# Untitled.net
KiCad netlist of a schematic drawn in EAGLE
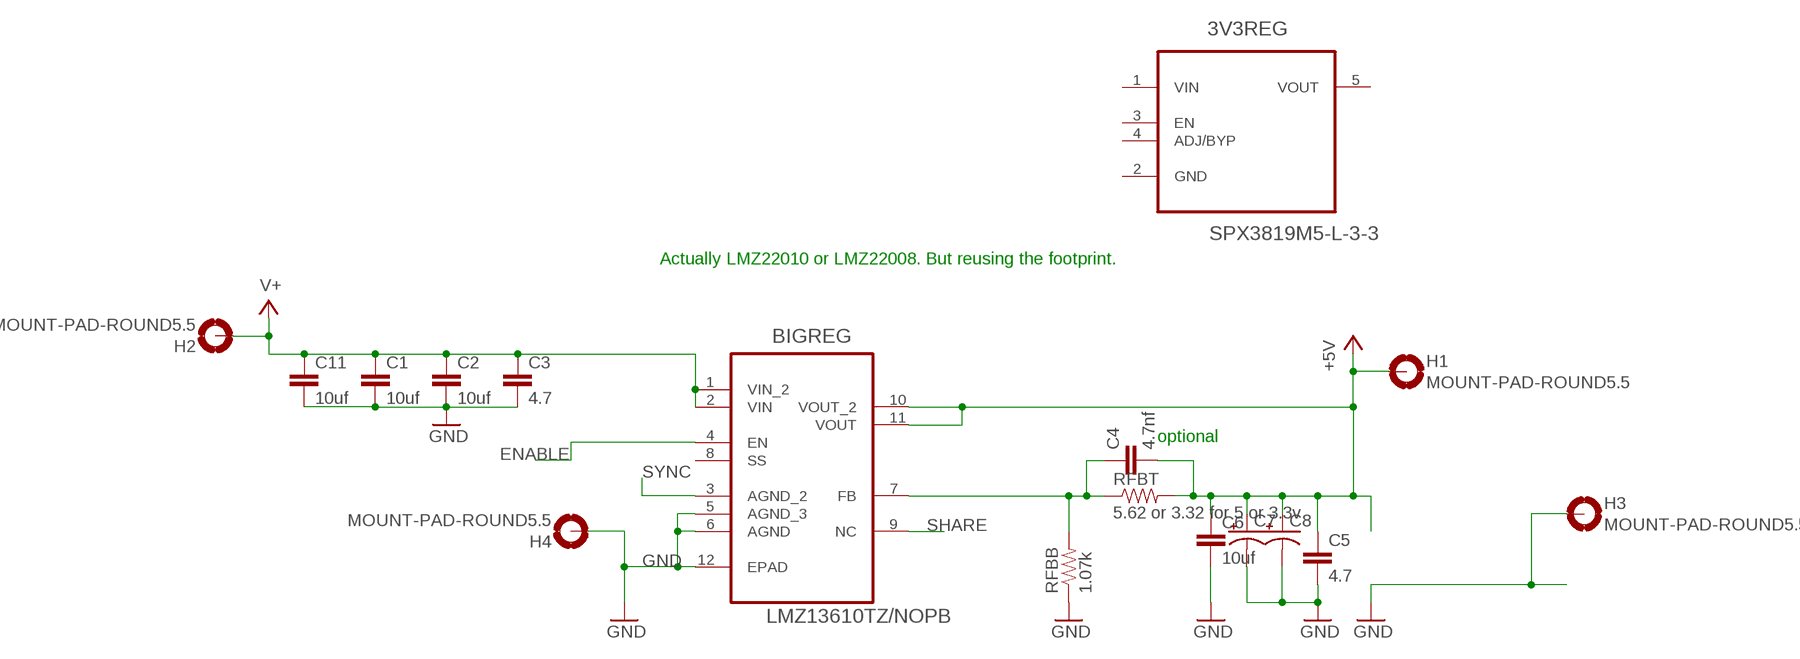
[diagram p0: schematic, sheet 1]

(export (version "E")
  (design (tool "Eeschema 10.0.6"))
  (components
    (comp (ref "3V3REG")
      (value "SPX3819M5-L-3-3")
      (footprint "eagle-import:SOT95P280X145-5N")
      (libsource (lib "eagle-import") (part "SPX3819M5-L-3-3"))
    )
    (comp (ref "BIGREG")
      (value "LMZ13610TZ/NOPB")
      (footprint "eagle-import:TI_TO-PMOD-11")
      (libsource (lib "eagle-import") (part "LMZ13610TZ/NOPB"))
    )
    (comp (ref "C1")
      (value "10uf")
      (footprint "eagle-import:1206")
      (libsource (lib "eagle-import") (part "CAP1206"))
    )
    (comp (ref "C2")
      (value "10uf")
      (footprint "eagle-import:1206")
      (libsource (lib "eagle-import") (part "CAP1206"))
    )
    (comp (ref "C3")
      (value "4.7")
      (footprint "eagle-import:1206")
      (libsource (lib "eagle-import") (part "CAP1206"))
    )
    (comp (ref "C4")
      (value "4.7nf")
      (footprint "eagle-import:0603-CAP")
      (libsource (lib "eagle-import") (part "SparkFun-Passives_CAP0603-CAP"))
    )
    (comp (ref "C5")
      (value "4.7")
      (footprint "eagle-import:1206")
      (libsource (lib "eagle-import") (part "CAP1206"))
    )
    (comp (ref "C6")
      (value "10uf")
      (footprint "eagle-import:1206")
      (libsource (lib "eagle-import") (part "CAP1206"))
    )
    (comp (ref "C7")
      (value "CAP_POLPTH2")
      (footprint "eagle-import:CPOL-RADIAL-10UF-25V")
      (libsource (lib "eagle-import") (part "CAP_POLPTH2"))
    )
    (comp (ref "C8")
      (value "CAP_POLPTH2")
      (footprint "eagle-import:CPOL-RADIAL-10UF-25V")
      (libsource (lib "eagle-import") (part "CAP_POLPTH2"))
    )
    (comp (ref "C11")
      (value "10uf")
      (footprint "eagle-import:1206")
      (libsource (lib "eagle-import") (part "CAP1206"))
    )
    (comp (ref "H1")
      (value "MOUNT-PAD-ROUND5.5")
      (footprint "eagle-import:5,5-PAD")
      (libsource (lib "eagle-import") (part "MOUNT-PAD-ROUND5.5"))
    )
    (comp (ref "H2")
      (value "MOUNT-PAD-ROUND5.5")
      (footprint "eagle-import:5,5-PAD")
      (libsource (lib "eagle-import") (part "MOUNT-PAD-ROUND5.5"))
    )
    (comp (ref "H3")
      (value "MOUNT-PAD-ROUND5.5")
      (footprint "eagle-import:5,5-PAD")
      (libsource (lib "eagle-import") (part "MOUNT-PAD-ROUND5.5"))
    )
    (comp (ref "H4")
      (value "MOUNT-PAD-ROUND5.5")
      (footprint "eagle-import:5,5-PAD")
      (libsource (lib "eagle-import") (part "MOUNT-PAD-ROUND5.5"))
    )
    (comp (ref "RFBB")
      (value "1.07k")
      (footprint "eagle-import:0603-RES")
      (libsource (lib "eagle-import") (part "RESISTOR0603"))
    )
    (comp (ref "RFBT")
      (value "5.62 or 3.32 for 5 or 3.3v")
      (footprint "eagle-import:0603-RES")
      (libsource (lib "eagle-import") (part "RESISTOR0603"))
    )
  )
  (nets
    (net (code "1") (name "+5V") (class "Default")
      (node (ref "BIGREG") (pin "10") (pinfunction "VOUT_2_10") (pintype "output"))
      (node (ref "BIGREG") (pin "11") (pinfunction "VOUT_11") (pintype "output"))
      (node (ref "C4") (pin "2") (pinfunction "2_2") (pintype "passive"))
      (node (ref "C5") (pin "1") (pinfunction "1_1") (pintype "passive"))
      (node (ref "C6") (pin "1") (pinfunction "1_1") (pintype "passive"))
      (node (ref "C7") (pin "1") (pinfunction "+_1") (pintype "passive"))
      (node (ref "C8") (pin "1") (pinfunction "+_1") (pintype "passive"))
      (node (ref "H1") (pin "B5,5") (pinfunction "MOUNT_B5,5") (pintype "passive"))
      (node (ref "RFBT") (pin "2") (pinfunction "2_2") (pintype "passive"))
    )
    (net (code "2") (name "/ENABLE") (class "Default")
      (node (ref "BIGREG") (pin "4") (pinfunction "EN_4") (pintype "input"))
    )
    (net (code "4") (name "/SYNC") (class "Default")
      (node (ref "BIGREG") (pin "3") (pinfunction "AGND_2_3") (pintype "passive"))
    )
    (net (code "5") (name "/VIN") (class "Default")
      (node (ref "3V3REG") (pin "1") (pinfunction "VIN_1") (pintype "power_in"))
    )
    (net (code "6") (name "GND") (class "Default")
      (node (ref "BIGREG") (pin "12") (pinfunction "EPAD_12") (pintype "passive"))
      (node (ref "BIGREG") (pin "5") (pinfunction "AGND_3_5") (pintype "passive"))
      (node (ref "BIGREG") (pin "6") (pinfunction "AGND_6") (pintype "passive"))
      (node (ref "C1") (pin "2") (pinfunction "2_2") (pintype "passive"))
      (node (ref "C11") (pin "2") (pinfunction "2_2") (pintype "passive"))
      (node (ref "C2") (pin "2") (pinfunction "2_2") (pintype "passive"))
      (node (ref "C3") (pin "2") (pinfunction "2_2") (pintype "passive"))
      (node (ref "C5") (pin "2") (pinfunction "2_2") (pintype "passive"))
      (node (ref "C6") (pin "2") (pinfunction "2_2") (pintype "passive"))
      (node (ref "C7") (pin "2") (pinfunction "-_2") (pintype "passive"))
      (node (ref "C8") (pin "2") (pinfunction "-_2") (pintype "passive"))
      (node (ref "H3") (pin "B5,5") (pinfunction "MOUNT_B5,5") (pintype "passive"))
      (node (ref "H4") (pin "B5,5") (pinfunction "MOUNT_B5,5") (pintype "passive"))
      (node (ref "RFBB") (pin "1") (pinfunction "1_1") (pintype "passive"))
    )
    (net (code "7") (name "Net-(BIGREG-FB)") (class "Default")
      (node (ref "BIGREG") (pin "7") (pinfunction "FB_7") (pintype "input"))
      (node (ref "C4") (pin "1") (pinfunction "1_1") (pintype "passive"))
      (node (ref "RFBB") (pin "2") (pinfunction "2_2") (pintype "passive"))
      (node (ref "RFBT") (pin "1") (pinfunction "1_1") (pintype "passive"))
    )
    (net (code "8") (name "V+") (class "Default")
      (node (ref "BIGREG") (pin "1") (pinfunction "VIN_2_1") (pintype "power_in"))
      (node (ref "BIGREG") (pin "2") (pinfunction "VIN_2") (pintype "power_in"))
      (node (ref "C1") (pin "1") (pinfunction "1_1") (pintype "passive"))
      (node (ref "C11") (pin "1") (pinfunction "1_1") (pintype "passive"))
      (node (ref "C2") (pin "1") (pinfunction "1_1") (pintype "passive"))
      (node (ref "C3") (pin "1") (pinfunction "1_1") (pintype "passive"))
      (node (ref "H2") (pin "B5,5") (pinfunction "MOUNT_B5,5") (pintype "passive"))
    )
    (net (code "9") (name "unconnected-(3V3REG-ADJ{slash}BYP-Pad4)") (class "Default")
      (node (ref "3V3REG") (pin "4") (pinfunction "ADJ/BYP_4") (pintype "passive"))
    )
    (net (code "10") (name "unconnected-(3V3REG-EN-Pad3)") (class "Default")
      (node (ref "3V3REG") (pin "3") (pinfunction "EN_3") (pintype "input"))
    )
    (net (code "11") (name "unconnected-(3V3REG-GND-Pad2)") (class "Default")
      (node (ref "3V3REG") (pin "2") (pinfunction "GND_2") (pintype "passive"))
    )
    (net (code "12") (name "unconnected-(3V3REG-VOUT-Pad5)") (class "Default")
      (node (ref "3V3REG") (pin "5") (pinfunction "VOUT_5") (pintype "output"))
    )
    (net (code "13") (name "unconnected-(BIGREG-NC-Pad9)") (class "Default")
      (node (ref "BIGREG") (pin "9") (pinfunction "NC_9") (pintype "no_connect"))
    )
    (net (code "14") (name "unconnected-(BIGREG-SS-Pad8)") (class "Default")
      (node (ref "BIGREG") (pin "8") (pinfunction "SS_8") (pintype "input"))
    )
  )
)
